# prod_board.net
KiCad netlist of a schematic drawn in EAGLE
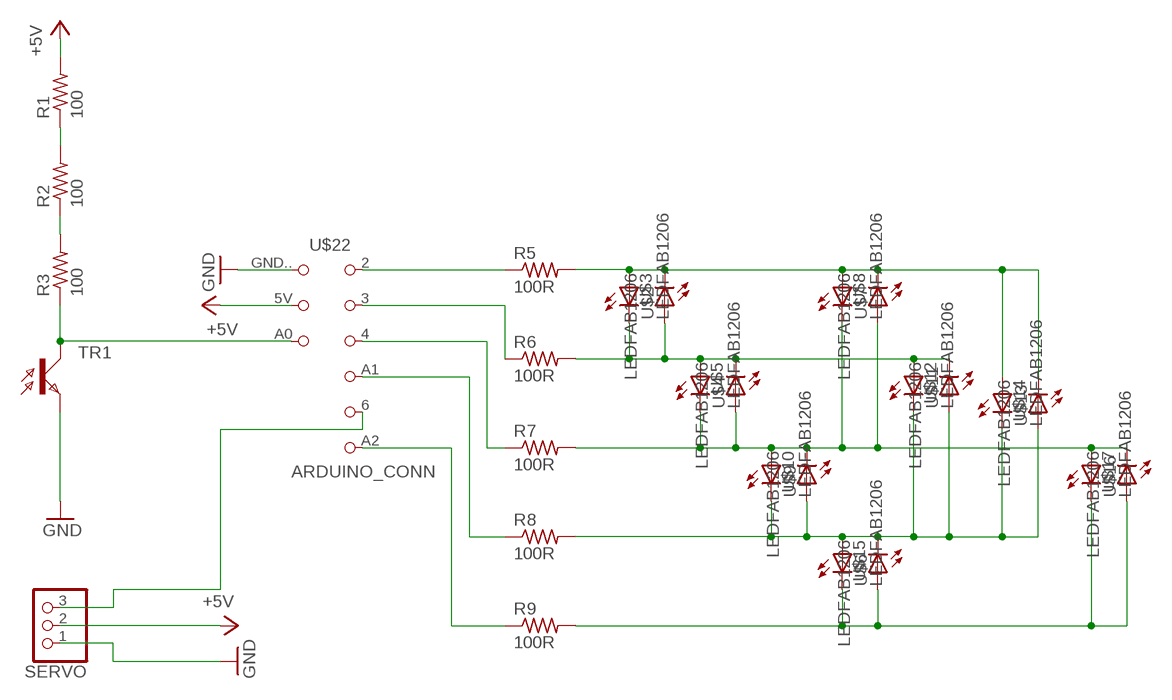
[diagram p0: schematic, sheet 1]

(export (version "E")
  (design (tool "Eeschema 10.0.6"))
  (components
    (comp (ref "R1")
      (value "100")
      (footprint "eagle-import:R1206FAB")
      (libsource (lib "eagle-import") (part "RES-US1206FAB"))
    )
    (comp (ref "R2")
      (value "100")
      (footprint "eagle-import:R1206FAB")
      (libsource (lib "eagle-import") (part "RES-US1206FAB"))
    )
    (comp (ref "R3")
      (value "100")
      (footprint "eagle-import:R1206FAB")
      (libsource (lib "eagle-import") (part "RES-US1206FAB"))
    )
    (comp (ref "R5")
      (value "100R")
      (footprint "eagle-import:R1206FAB")
      (libsource (lib "eagle-import") (part "RES-US1206FAB"))
    )
    (comp (ref "R6")
      (value "100R")
      (footprint "eagle-import:R1206FAB")
      (libsource (lib "eagle-import") (part "RES-US1206FAB"))
    )
    (comp (ref "R7")
      (value "100R")
      (footprint "eagle-import:R1206FAB")
      (libsource (lib "eagle-import") (part "RES-US1206FAB"))
    )
    (comp (ref "R8")
      (value "100R")
      (footprint "eagle-import:R1206FAB")
      (libsource (lib "eagle-import") (part "RES-US1206FAB"))
    )
    (comp (ref "R9")
      (value "100R")
      (footprint "eagle-import:R1206FAB")
      (libsource (lib "eagle-import") (part "RES-US1206FAB"))
    )
    (comp (ref "SERVO")
      (value "PINHD-1X3")
      (footprint "eagle-import:1X03")
      (libsource (lib "eagle-import") (part "PINHD-1X3"))
    )
    (comp (ref "TR1")
      (value "PHOTOTRANSISTOR-NPN1206")
      (footprint "eagle-import:OP1206")
      (libsource (lib "eagle-import") (part "PHOTOTRANSISTOR-NPN1206"))
    )
    (comp (ref "U$2")
      (value "LEDFAB1206")
      (footprint "eagle-import:LED1206FAB")
      (libsource (lib "eagle-import") (part "LEDFAB1206"))
    )
    (comp (ref "U$3")
      (value "LEDFAB1206")
      (footprint "eagle-import:LED1206FAB")
      (libsource (lib "eagle-import") (part "LEDFAB1206"))
    )
    (comp (ref "U$4")
      (value "LEDFAB1206")
      (footprint "eagle-import:LED1206FAB")
      (libsource (lib "eagle-import") (part "LEDFAB1206"))
    )
    (comp (ref "U$5")
      (value "LEDFAB1206")
      (footprint "eagle-import:LED1206FAB")
      (libsource (lib "eagle-import") (part "LEDFAB1206"))
    )
    (comp (ref "U$6")
      (value "LEDFAB1206")
      (footprint "eagle-import:LED1206FAB")
      (libsource (lib "eagle-import") (part "LEDFAB1206"))
    )
    (comp (ref "U$7")
      (value "LEDFAB1206")
      (footprint "eagle-import:LED1206FAB")
      (libsource (lib "eagle-import") (part "LEDFAB1206"))
    )
    (comp (ref "U$8")
      (value "LEDFAB1206")
      (footprint "eagle-import:LED1206FAB")
      (libsource (lib "eagle-import") (part "LEDFAB1206"))
    )
    (comp (ref "U$9")
      (value "LEDFAB1206")
      (footprint "eagle-import:LED1206FAB")
      (libsource (lib "eagle-import") (part "LEDFAB1206"))
    )
    (comp (ref "U$10")
      (value "LEDFAB1206")
      (footprint "eagle-import:LED1206FAB")
      (libsource (lib "eagle-import") (part "LEDFAB1206"))
    )
    (comp (ref "U$11")
      (value "LEDFAB1206")
      (footprint "eagle-import:LED1206FAB")
      (libsource (lib "eagle-import") (part "LEDFAB1206"))
    )
    (comp (ref "U$12")
      (value "LEDFAB1206")
      (footprint "eagle-import:LED1206FAB")
      (libsource (lib "eagle-import") (part "LEDFAB1206"))
    )
    (comp (ref "U$13")
      (value "LEDFAB1206")
      (footprint "eagle-import:LED1206FAB")
      (libsource (lib "eagle-import") (part "LEDFAB1206"))
    )
    (comp (ref "U$14")
      (value "LEDFAB1206")
      (footprint "eagle-import:LED1206FAB")
      (libsource (lib "eagle-import") (part "LEDFAB1206"))
    )
    (comp (ref "U$15")
      (value "LEDFAB1206")
      (footprint "eagle-import:LED1206FAB")
      (libsource (lib "eagle-import") (part "LEDFAB1206"))
    )
    (comp (ref "U$16")
      (value "LEDFAB1206")
      (footprint "eagle-import:LED1206FAB")
      (libsource (lib "eagle-import") (part "LEDFAB1206"))
    )
    (comp (ref "U$17")
      (value "LEDFAB1206")
      (footprint "eagle-import:LED1206FAB")
      (libsource (lib "eagle-import") (part "LEDFAB1206"))
    )
    (comp (ref "U$22")
      (value "ARDUINO_CONN")
      (footprint "eagle-import:ARDUINO_UNO")
      (libsource (lib "eagle-import") (part "ARDUINO_CONN"))
    )
  )
  (nets
    (net (code "1") (name "+5V") (class "Default")
      (node (ref "R1") (pin "2") (pinfunction "2_2") (pintype "passive"))
      (node (ref "SERVO") (pin "2") (pinfunction "2_2") (pintype "passive"))
      (node (ref "U$22") (pin "5V") (pinfunction "5V_5V") (pintype "passive"))
    )
    (net (code "2") (name "GND") (class "Default")
      (node (ref "SERVO") (pin "1") (pinfunction "1_1") (pintype "passive"))
      (node (ref "TR1") (pin "E") (pinfunction "E_E") (pintype "passive"))
      (node (ref "U$22") (pin "GND..") (pinfunction "GND_GND..") (pintype "passive"))
    )
    (net (code "3") (name "Net-(R1-Pad1)") (class "Default")
      (node (ref "R1") (pin "1") (pinfunction "1_1") (pintype "passive"))
      (node (ref "R2") (pin "2") (pinfunction "2_2") (pintype "passive"))
    )
    (net (code "4") (name "Net-(R2-Pad1)") (class "Default")
      (node (ref "R2") (pin "1") (pinfunction "1_1") (pintype "passive"))
      (node (ref "R3") (pin "2") (pinfunction "2_2") (pintype "passive"))
    )
    (net (code "5") (name "Net-(R3-Pad1)") (class "Default")
      (node (ref "R3") (pin "1") (pinfunction "1_1") (pintype "passive"))
      (node (ref "TR1") (pin "C") (pinfunction "C_C") (pintype "passive"))
      (node (ref "U$22") (pin "A0") (pinfunction "A0_A0") (pintype "passive"))
    )
    (net (code "6") (name "Net-(U$10-A)") (class "Default")
      (node (ref "R8") (pin "2") (pinfunction "2_2") (pintype "passive"))
      (node (ref "U$10") (pin "1") (pinfunction "A_1") (pintype "passive"))
      (node (ref "U$11") (pin "2") (pinfunction "C_2") (pintype "passive"))
      (node (ref "U$12") (pin "1") (pinfunction "A_1") (pintype "passive"))
      (node (ref "U$13") (pin "2") (pinfunction "C_2") (pintype "passive"))
      (node (ref "U$14") (pin "1") (pinfunction "A_1") (pintype "passive"))
      (node (ref "U$15") (pin "2") (pinfunction "C_2") (pintype "passive"))
      (node (ref "U$6") (pin "1") (pinfunction "A_1") (pintype "passive"))
      (node (ref "U$9") (pin "2") (pinfunction "C_2") (pintype "passive"))
    )
    (net (code "7") (name "Net-(U$10-C)") (class "Default")
      (node (ref "R7") (pin "2") (pinfunction "2_2") (pintype "passive"))
      (node (ref "U$10") (pin "2") (pinfunction "C_2") (pintype "passive"))
      (node (ref "U$16") (pin "1") (pinfunction "A_1") (pintype "passive"))
      (node (ref "U$17") (pin "2") (pinfunction "C_2") (pintype "passive"))
      (node (ref "U$4") (pin "2") (pinfunction "C_2") (pintype "passive"))
      (node (ref "U$5") (pin "1") (pinfunction "A_1") (pintype "passive"))
      (node (ref "U$7") (pin "2") (pinfunction "C_2") (pintype "passive"))
      (node (ref "U$8") (pin "1") (pinfunction "A_1") (pintype "passive"))
      (node (ref "U$9") (pin "1") (pinfunction "A_1") (pintype "passive"))
    )
    (net (code "8") (name "Net-(U$11-A)") (class "Default")
      (node (ref "R6") (pin "2") (pinfunction "2_2") (pintype "passive"))
      (node (ref "U$11") (pin "1") (pinfunction "A_1") (pintype "passive"))
      (node (ref "U$12") (pin "2") (pinfunction "C_2") (pintype "passive"))
      (node (ref "U$2") (pin "2") (pinfunction "C_2") (pintype "passive"))
      (node (ref "U$3") (pin "1") (pinfunction "A_1") (pintype "passive"))
      (node (ref "U$4") (pin "1") (pinfunction "A_1") (pintype "passive"))
      (node (ref "U$5") (pin "2") (pinfunction "C_2") (pintype "passive"))
    )
    (net (code "9") (name "Net-(U$13-A)") (class "Default")
      (node (ref "R5") (pin "2") (pinfunction "2_2") (pintype "passive"))
      (node (ref "U$13") (pin "1") (pinfunction "A_1") (pintype "passive"))
      (node (ref "U$14") (pin "2") (pinfunction "C_2") (pintype "passive"))
      (node (ref "U$2") (pin "1") (pinfunction "A_1") (pintype "passive"))
      (node (ref "U$3") (pin "2") (pinfunction "C_2") (pintype "passive"))
      (node (ref "U$7") (pin "1") (pinfunction "A_1") (pintype "passive"))
      (node (ref "U$8") (pin "2") (pinfunction "C_2") (pintype "passive"))
    )
    (net (code "10") (name "Net-(U$15-A)") (class "Default")
      (node (ref "R9") (pin "2") (pinfunction "2_2") (pintype "passive"))
      (node (ref "U$15") (pin "1") (pinfunction "A_1") (pintype "passive"))
      (node (ref "U$16") (pin "2") (pinfunction "C_2") (pintype "passive"))
      (node (ref "U$17") (pin "1") (pinfunction "A_1") (pintype "passive"))
      (node (ref "U$6") (pin "2") (pinfunction "C_2") (pintype "passive"))
    )
    (net (code "11") (name "Net-(U$22-D2)") (class "Default")
      (node (ref "R5") (pin "1") (pinfunction "1_1") (pintype "passive"))
      (node (ref "U$22") (pin "2") (pinfunction "D2_2") (pintype "passive"))
    )
    (net (code "12") (name "Net-(U$22-D3)") (class "Default")
      (node (ref "R6") (pin "1") (pinfunction "1_1") (pintype "passive"))
      (node (ref "U$22") (pin "3") (pinfunction "D3_3") (pintype "passive"))
    )
    (net (code "13") (name "Net-(U$22-D4)") (class "Default")
      (node (ref "R7") (pin "1") (pinfunction "1_1") (pintype "passive"))
      (node (ref "U$22") (pin "4") (pinfunction "D4_4") (pintype "passive"))
    )
    (net (code "14") (name "Net-(U$22-D5)") (class "Default")
      (node (ref "R8") (pin "1") (pinfunction "1_1") (pintype "passive"))
      (node (ref "U$22") (pin "A1") (pinfunction "D5_A1") (pintype "passive"))
    )
    (net (code "15") (name "Net-(U$22-D6)") (class "Default")
      (node (ref "SERVO") (pin "3") (pinfunction "3_3") (pintype "passive"))
      (node (ref "U$22") (pin "6") (pinfunction "D6_6") (pintype "passive"))
    )
    (net (code "16") (name "Net-(U$22-D7)") (class "Default")
      (node (ref "R9") (pin "1") (pinfunction "1_1") (pintype "passive"))
      (node (ref "U$22") (pin "A2") (pinfunction "D7_A2") (pintype "passive"))
    )
  )
)
